# XmasLights.net
KiCad netlist of a schematic drawn in Altium Designer
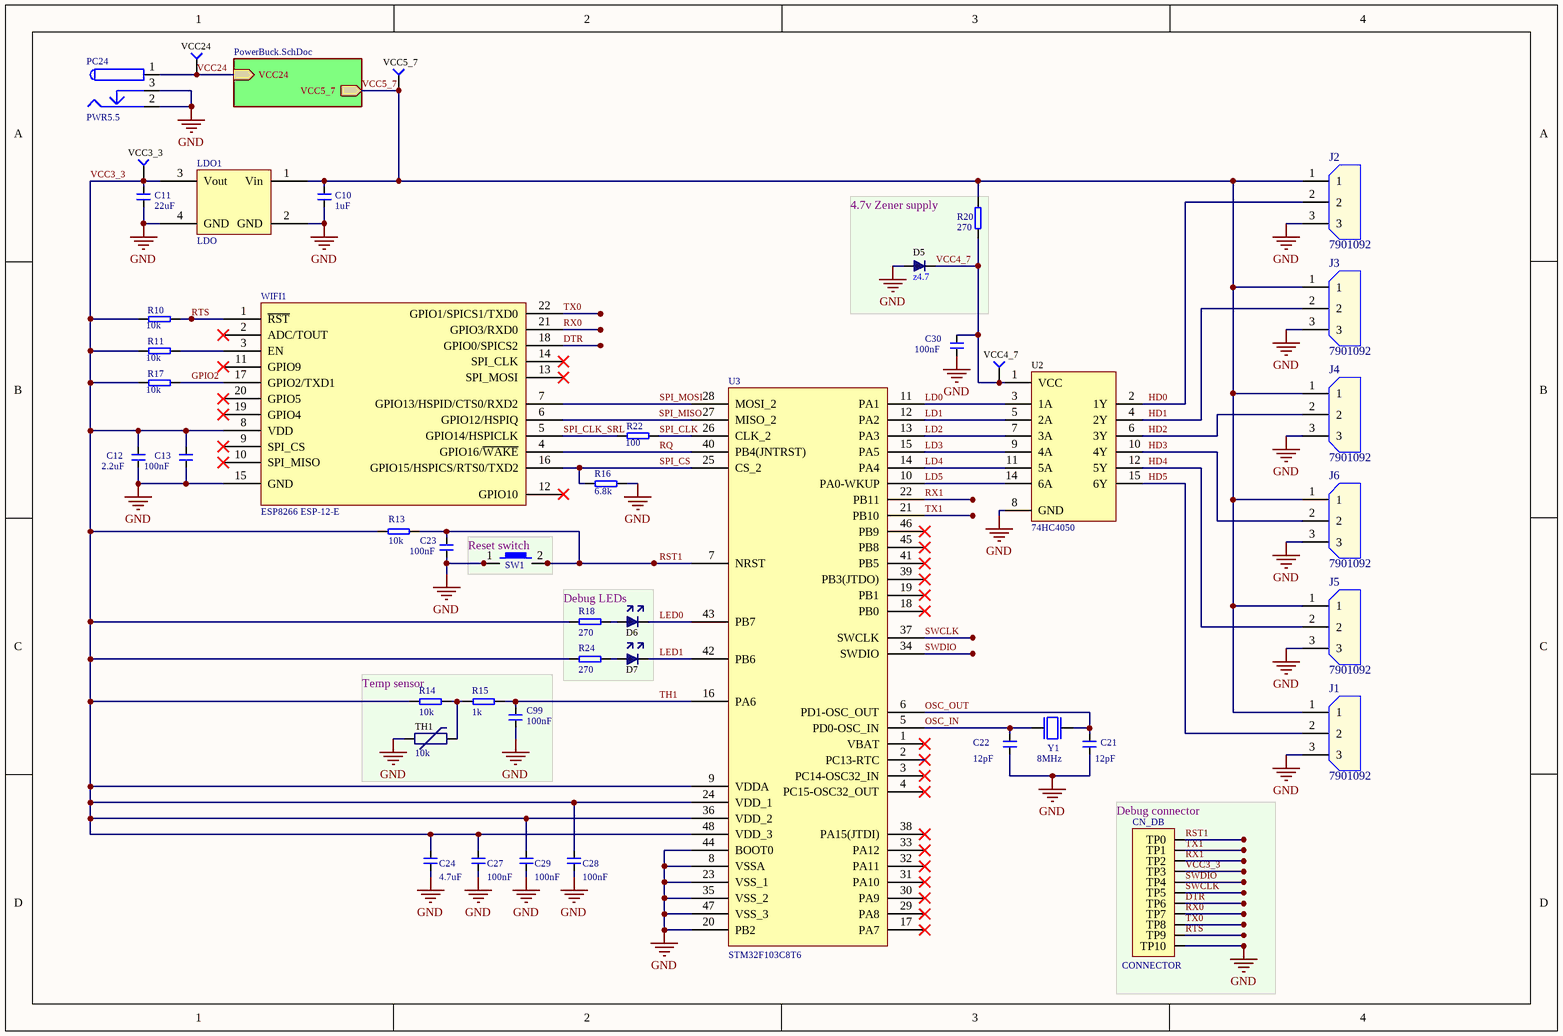
[diagram p0: XmasLights.SchDoc]

(export (version "E")
  (design (tool "Eeschema 10.0.6"))
  (components
    (comp (ref "C10")
      (value "1uF")
      (footprint "CAP_1206")
      (description "Capacitor")
      (libsource (lib "Controller") (part "CAP"))
    )
    (comp (ref "C11")
      (value "22uF")
      (footprint "Controller:CAP_1206")
      (description "Capacitor")
      (libsource (lib "Controller") (part "CAP"))
    )
    (comp (ref "C12")
      (value "2.2uF")
      (footprint "Controller:CAP 0603/1608")
      (description "Capacitor")
      (libsource (lib "Controller") (part "CAP"))
    )
    (comp (ref "C13")
      (value "100nF")
      (footprint "Controller:CAP 0603/1608")
      (description "Capacitor")
      (libsource (lib "Controller") (part "CAP"))
    )
    (comp (ref "C21")
      (value "12pF")
      (footprint "Controller:CAP 0603/1608")
      (description "Capacitor")
      (libsource (lib "Controller") (part "CAP"))
    )
    (comp (ref "C22")
      (value "12pF")
      (footprint "Controller:CAP 0603/1608")
      (description "Capacitor")
      (libsource (lib "Controller") (part "CAP"))
    )
    (comp (ref "C23")
      (value "100nF")
      (footprint "Controller:CAP 0603/1608")
      (description "Capacitor")
      (libsource (lib "Controller") (part "CAP"))
    )
    (comp (ref "C24")
      (value "4.7uF")
      (footprint "Controller:CAP 0603/1608")
      (description "Capacitor")
      (libsource (lib "Controller") (part "CAP"))
    )
    (comp (ref "C27")
      (value "100nF")
      (footprint "Controller:CAP 0603/1608")
      (description "Capacitor")
      (libsource (lib "Controller") (part "CAP"))
    )
    (comp (ref "C28")
      (value "100nF")
      (footprint "Controller:CAP 0603/1608")
      (description "Capacitor")
      (libsource (lib "Controller") (part "CAP"))
    )
    (comp (ref "C29")
      (value "100nF")
      (footprint "Controller:CAP 0603/1608")
      (description "Capacitor")
      (libsource (lib "Controller") (part "CAP"))
    )
    (comp (ref "C30")
      (value "100nF")
      (footprint "Controller:CAP 0603/1608")
      (description "Capacitor")
      (libsource (lib "Controller") (part "CAP"))
    )
    (comp (ref "C99")
      (value "100nF")
      (footprint "Controller:CAP 0603/1608")
      (description "Capacitor")
      (libsource (lib "Controller") (part "CAP"))
    )
    (comp (ref "CN_DB")
      (value "CONNECTOR")
      (footprint "Controller:Edge Connector")
      (description "Debug Connector")
      (libsource (lib "Controller") (part "CONNECTOR"))
    )
    (comp (ref "D5")
      (value "z4.7")
      (footprint "Controller:SOD2512X110N")
      (libsource (lib "Controller") (part "DIODE"))
    )
    (comp (ref "D6")
      (value "LED")
      (footprint "controller:Chip2PinSM127P600-8N")
      (libsource (lib "Controller") (part "LED"))
    )
    (comp (ref "D7")
      (value "LED")
      (footprint "controller:Chip2PinSM127P600-8N")
      (libsource (lib "Controller") (part "LED"))
    )
    (comp (ref "J1") (value "7901092") (footprint "7901092") (libsource (lib "Controller") (part "7901092")))
    (comp (ref "J2") (value "7901092") (footprint "7901092") (libsource (lib "Controller") (part "7901092")))
    (comp (ref "J3") (value "7901092") (footprint "7901092") (libsource (lib "Controller") (part "7901092")))
    (comp (ref "J4") (value "7901092") (footprint "7901092") (libsource (lib "Controller") (part "7901092")))
    (comp (ref "J5") (value "7901092") (footprint "7901092") (libsource (lib "Controller") (part "7901092")))
    (comp (ref "J6") (value "7901092") (footprint "7901092") (libsource (lib "Controller") (part "7901092")))
    (comp (ref "LDO1")
      (value "LDO")
      (footprint "Controller:SOT230P700X180-4N")
      (description "LDO Voltage Regulator")
      (libsource (lib "Controller") (part "LDO"))
    )
    (comp (ref "PC24")
      (value "PWR5.5")
      (footprint "Controller:DC_CON")
      (description "Low Voltage Power Supply Connector")
      (fields (field (name "PUBLISHER") "Altium Limited"))
      (libsource (lib "Controller") (part "PWR2.5"))
    )
    (comp (ref "R10")
      (value "10k")
      (footprint "Controller:RES 0603/1608")
      (description "Resistor")
      (libsource (lib "Controller") (part "RES"))
    )
    (comp (ref "R11")
      (value "10k")
      (footprint "Controller:RES 0603/1608")
      (description "Resistor")
      (libsource (lib "Controller") (part "RES"))
    )
    (comp (ref "R13")
      (value "10k")
      (footprint "Controller:RES 0603/1608")
      (description "Resistor")
      (libsource (lib "Controller") (part "RES"))
    )
    (comp (ref "R14")
      (value "10k")
      (footprint "controller:RES 0603/1608")
      (description "Resistor")
      (libsource (lib "Controller") (part "RES"))
    )
    (comp (ref "R15")
      (value "1k")
      (footprint "controller:RES 0603/1608")
      (description "Resistor")
      (libsource (lib "Controller") (part "RES"))
    )
    (comp (ref "R16")
      (value "6.8k")
      (footprint "Controller:RES 0603/1608")
      (description "Resistor")
      (libsource (lib "Controller") (part "RES"))
    )
    (comp (ref "R17")
      (value "10k")
      (footprint "Controller:RES 0603/1608")
      (description "Resistor")
      (libsource (lib "Controller") (part "RES"))
    )
    (comp (ref "R18")
      (value "270")
      (footprint "Controller:RES 0603/1608")
      (description "Resistor")
      (libsource (lib "Controller") (part "RES"))
    )
    (comp (ref "R20")
      (value "270")
      (footprint "Controller:RES 0603/1608")
      (description "Resistor")
      (libsource (lib "Controller") (part "RES"))
    )
    (comp (ref "R22")
      (value "100")
      (footprint "Controller:RES 0603/1608")
      (description "Resistor")
      (libsource (lib "Controller") (part "RES"))
    )
    (comp (ref "R24")
      (value "270")
      (footprint "Controller:RES 0603/1608")
      (description "Resistor")
      (libsource (lib "Controller") (part "RES"))
    )
    (comp (ref "SW1")
      (value "SWITCH")
      (footprint "Controller:FSM-SWITCH")
      (description "6x6mm SMD tactile switch,5mm H 1.6N Black Button Tactile Switch, SPST-NO 0.05 A@ 12 V dc 1.4mm")
      (fields
        (field (name "RS PART NUMBER") "1616046")
        (field (name "MANUFACTURER_PART_NUMBER") "4-1437565-1")
      )
      (libsource (lib "Controller") (part "4-1437565-1"))
    )
    (comp (ref "TH1")
      (value "10k")
      (footprint "Controller:CAP 0603/1608")
      (libsource (lib "Controller") (part "THERMISTOR"))
    )
    (comp (ref "U2")
      (value "74HC4050")
      (footprint "SOIC127P600X175-16N")
      (libsource (lib "Controller") (part "74HC4050"))
    )
    (comp (ref "U3")
      (value "STM32F103C8T6")
      (footprint "Controller:CQFP50P900X900X160-48N")
      (libsource (lib "Controller") (part "STM32F103C8T6"))
    )
    (comp (ref "VCC3_3")
      (value "TESTPOINT")
      (footprint "TESTPOINT")
      (libsource (lib "Controller") (part "TESTPOINT"))
    )
    (comp (ref "VCC4_7")
      (value "TESTPOINT")
      (footprint "TESTPOINT")
      (libsource (lib "Controller") (part "TESTPOINT"))
    )
    (comp (ref "VCC5_7")
      (value "TESTPOINT")
      (footprint "TESTPOINT")
      (libsource (lib "Controller") (part "TESTPOINT"))
    )
    (comp (ref "VCC24")
      (value "TESTPOINT")
      (footprint "TESTPOINT")
      (libsource (lib "Controller") (part "TESTPOINT"))
    )
    (comp (ref "WIFI1")
      (value "ESP8266 ESP-12-E")
      (footprint "ESP8266:ESP8266 ESP-12-E")
      (libsource (lib "Controller") (part "ESP8266 ESP-12-E"))
    )
    (comp (ref "Y1")
      (value "8MHz")
      (footprint "CRYSTAL")
      (description "Cheapo SMT Crystal")
      (libsource (lib "Controller") (part "CRYSTAL"))
    )
  )
  (nets
    (net (code "1") (name "/DTR") (class "Default")
      (node (ref "CN_DB") (pin "7") (pinfunction "TP6_7") (pintype "passive"))
      (node (ref "WIFI1") (pin "18") (pinfunction "GPIO0/SPICS2_18") (pintype "passive"))
    )
    (net (code "2") (name "/GPIO2") (class "Default")
      (node (ref "R17") (pin "2") (pinfunction "2_2") (pintype "passive"))
      (node (ref "WIFI1") (pin "17") (pinfunction "GPIO2/TXD1_17") (pintype "passive"))
    )
    (net (code "3") (name "/HD0") (class "Default")
      (node (ref "J2") (pin "2") (pinfunction "2_2") (pintype "passive"))
      (node (ref "U2") (pin "2") (pinfunction "1Y_2") (pintype "passive"))
    )
    (net (code "4") (name "/HD1") (class "Default")
      (node (ref "J3") (pin "2") (pinfunction "2_2") (pintype "passive"))
      (node (ref "U2") (pin "4") (pinfunction "2Y_4") (pintype "passive"))
    )
    (net (code "5") (name "/HD2") (class "Default")
      (node (ref "J4") (pin "2") (pinfunction "2_2") (pintype "passive"))
      (node (ref "U2") (pin "6") (pinfunction "3Y_6") (pintype "passive"))
    )
    (net (code "6") (name "/HD3") (class "Default")
      (node (ref "J6") (pin "2") (pinfunction "2_2") (pintype "passive"))
      (node (ref "U2") (pin "10") (pinfunction "4Y_10") (pintype "passive"))
    )
    (net (code "7") (name "/HD4") (class "Default")
      (node (ref "J5") (pin "2") (pinfunction "2_2") (pintype "passive"))
      (node (ref "U2") (pin "12") (pinfunction "5Y_12") (pintype "passive"))
    )
    (net (code "8") (name "/HD5") (class "Default")
      (node (ref "J1") (pin "2") (pinfunction "2_2") (pintype "passive"))
      (node (ref "U2") (pin "15") (pinfunction "6Y_15") (pintype "passive"))
    )
    (net (code "9") (name "/LD0") (class "Default")
      (node (ref "U2") (pin "3") (pinfunction "1A_3") (pintype "passive"))
      (node (ref "U3") (pin "11") (pinfunction "PA1_11") (pintype "passive"))
    )
    (net (code "10") (name "/LD1") (class "Default")
      (node (ref "U2") (pin "5") (pinfunction "2A_5") (pintype "passive"))
      (node (ref "U3") (pin "12") (pinfunction "PA2_12") (pintype "passive"))
    )
    (net (code "11") (name "/LD2") (class "Default")
      (node (ref "U2") (pin "7") (pinfunction "3A_7") (pintype "passive"))
      (node (ref "U3") (pin "13") (pinfunction "PA3_13") (pintype "passive"))
    )
    (net (code "12") (name "/LD3") (class "Default")
      (node (ref "U2") (pin "9") (pinfunction "4A_9") (pintype "passive"))
      (node (ref "U3") (pin "15") (pinfunction "PA5_15") (pintype "passive"))
    )
    (net (code "13") (name "/LD4") (class "Default")
      (node (ref "U2") (pin "11") (pinfunction "5A_11") (pintype "passive"))
      (node (ref "U3") (pin "14") (pinfunction "PA4_14") (pintype "passive"))
    )
    (net (code "14") (name "/LD5") (class "Default")
      (node (ref "U2") (pin "14") (pinfunction "6A_14") (pintype "passive"))
      (node (ref "U3") (pin "10") (pinfunction "PA0-WKUP_10") (pintype "passive"))
    )
    (net (code "15") (name "/LED0") (class "Default")
      (node (ref "D6") (pin "2") (pinfunction "ANODE_2") (pintype "passive"))
      (node (ref "U3") (pin "43") (pinfunction "PB7_43") (pintype "passive"))
    )
    (net (code "16") (name "/LED1") (class "Default")
      (node (ref "D7") (pin "2") (pinfunction "ANODE_2") (pintype "passive"))
      (node (ref "U3") (pin "42") (pinfunction "PB6_42") (pintype "passive"))
    )
    (net (code "17") (name "/OSC_IN") (class "Default")
      (node (ref "C22") (pin "2") (pinfunction "2_2") (pintype "passive"))
      (node (ref "U3") (pin "5") (pinfunction "PD0-OSC_IN_5") (pintype "passive"))
      (node (ref "Y1") (pin "1") (pinfunction "1_1") (pintype "passive"))
    )
    (net (code "18") (name "/OSC_OUT") (class "Default")
      (node (ref "C21") (pin "2") (pinfunction "2_2") (pintype "passive"))
      (node (ref "U3") (pin "6") (pinfunction "PD1-OSC_OUT_6") (pintype "passive"))
      (node (ref "Y1") (pin "2") (pinfunction "2_2") (pintype "passive"))
    )
    (net (code "19") (name "/RQ") (class "Default")
      (node (ref "U3") (pin "40") (pinfunction "PB4(JNTRST)_40") (pintype "passive"))
      (node (ref "WIFI1") (pin "4") (pinfunction "GPIO16/~{WAKE}_4") (pintype "passive"))
    )
    (net (code "20") (name "/RST1") (class "Default")
      (node (ref "C23") (pin "1") (pinfunction "1_1") (pintype "passive"))
      (node (ref "CN_DB") (pin "1") (pinfunction "TP0_1") (pintype "passive"))
      (node (ref "R13") (pin "2") (pinfunction "2_2") (pintype "passive"))
      (node (ref "SW1") (pin "2") (pinfunction "2_2") (pintype "passive"))
      (node (ref "SW1") (pin "4") (pinfunction "4_4") (pintype "passive"))
      (node (ref "U3") (pin "7") (pinfunction "NRST_7") (pintype "passive"))
    )
    (net (code "21") (name "/RTS") (class "Default")
      (node (ref "CN_DB") (pin "10") (pinfunction "TP9_10") (pintype "passive"))
      (node (ref "R10") (pin "2") (pinfunction "2_2") (pintype "passive"))
      (node (ref "WIFI1") (pin "1") (pinfunction "~{RST}_1") (pintype "passive"))
    )
    (net (code "22") (name "/RX0") (class "Default")
      (node (ref "CN_DB") (pin "8") (pinfunction "TP7_8") (pintype "passive"))
      (node (ref "WIFI1") (pin "21") (pinfunction "GPIO3/RXD0_21") (pintype "passive"))
    )
    (net (code "23") (name "/RX1") (class "Default")
      (node (ref "CN_DB") (pin "3") (pinfunction "TP2_3") (pintype "passive"))
      (node (ref "U3") (pin "22") (pinfunction "PB11_22") (pintype "passive"))
    )
    (net (code "24") (name "/SPI_CLK") (class "Default")
      (node (ref "R22") (pin "2") (pinfunction "2_2") (pintype "passive"))
      (node (ref "U3") (pin "26") (pinfunction "CLK_2_26") (pintype "passive"))
    )
    (net (code "25") (name "/SPI_CLK_SRL") (class "Default")
      (node (ref "R22") (pin "1") (pinfunction "1_1") (pintype "passive"))
      (node (ref "WIFI1") (pin "5") (pinfunction "GPIO14/HSPICLK_5") (pintype "passive"))
    )
    (net (code "26") (name "/SPI_CS") (class "Default")
      (node (ref "R16") (pin "2") (pinfunction "2_2") (pintype "passive"))
      (node (ref "U3") (pin "25") (pinfunction "CS_2_25") (pintype "passive"))
      (node (ref "WIFI1") (pin "16") (pinfunction "GPIO15/HSPICS/RTS0/TXD2_16") (pintype "passive"))
    )
    (net (code "27") (name "/SPI_MISO") (class "Default")
      (node (ref "U3") (pin "27") (pinfunction "MISO_2_27") (pintype "passive"))
      (node (ref "WIFI1") (pin "6") (pinfunction "GPIO12/HSPIQ_6") (pintype "passive"))
    )
    (net (code "28") (name "/SPI_MOSI") (class "Default")
      (node (ref "U3") (pin "28") (pinfunction "MOSI_2_28") (pintype "passive"))
      (node (ref "WIFI1") (pin "7") (pinfunction "GPIO13/HSPID/CTS0/RXD2_7") (pintype "passive"))
    )
    (net (code "29") (name "/SWCLK") (class "Default")
      (node (ref "CN_DB") (pin "6") (pinfunction "TP5_6") (pintype "passive"))
      (node (ref "U3") (pin "37") (pinfunction "SWCLK_37") (pintype "passive"))
    )
    (net (code "30") (name "/SWDIO") (class "Default")
      (node (ref "CN_DB") (pin "5") (pinfunction "TP4_5") (pintype "passive"))
      (node (ref "U3") (pin "34") (pinfunction "SWDIO_34") (pintype "passive"))
    )
    (net (code "31") (name "/TH1") (class "Default")
      (node (ref "C99") (pin "2") (pinfunction "2_2") (pintype "passive"))
      (node (ref "R15") (pin "1") (pinfunction "1_1") (pintype "passive"))
      (node (ref "U3") (pin "16") (pinfunction "PA6_16") (pintype "passive"))
    )
    (net (code "32") (name "/TX0") (class "Default")
      (node (ref "CN_DB") (pin "9") (pinfunction "TP8_9") (pintype "passive"))
      (node (ref "WIFI1") (pin "22") (pinfunction "GPIO1/SPICS1/TXD0_22") (pintype "passive"))
    )
    (net (code "33") (name "/TX1") (class "Default")
      (node (ref "CN_DB") (pin "2") (pinfunction "TP1_2") (pintype "passive"))
      (node (ref "U3") (pin "21") (pinfunction "PB10_21") (pintype "passive"))
    )
    (net (code "34") (name "/VCC3_3") (class "Default")
      (node (ref "C11") (pin "1") (pinfunction "1_1") (pintype "passive"))
      (node (ref "C12") (pin "1") (pinfunction "1_1") (pintype "passive"))
      (node (ref "C13") (pin "1") (pinfunction "1_1") (pintype "passive"))
      (node (ref "C24") (pin "1") (pinfunction "1_1") (pintype "passive"))
      (node (ref "C27") (pin "1") (pinfunction "1_1") (pintype "passive"))
      (node (ref "C28") (pin "1") (pinfunction "1_1") (pintype "passive"))
      (node (ref "C29") (pin "1") (pinfunction "1_1") (pintype "passive"))
      (node (ref "CN_DB") (pin "4") (pinfunction "TP3_4") (pintype "passive"))
      (node (ref "LDO1") (pin "3") (pinfunction "Vout_3") (pintype "passive"))
      (node (ref "R10") (pin "1") (pinfunction "1_1") (pintype "passive"))
      (node (ref "R11") (pin "1") (pinfunction "1_1") (pintype "passive"))
      (node (ref "R13") (pin "1") (pinfunction "1_1") (pintype "passive"))
      (node (ref "R14") (pin "1") (pinfunction "1_1") (pintype "passive"))
      (node (ref "R17") (pin "1") (pinfunction "1_1") (pintype "passive"))
      (node (ref "R18") (pin "1") (pinfunction "1_1") (pintype "passive"))
      (node (ref "R24") (pin "1") (pinfunction "1_1") (pintype "passive"))
      (node (ref "U3") (pin "24") (pinfunction "VDD_1_24") (pintype "passive"))
      (node (ref "U3") (pin "36") (pinfunction "VDD_2_36") (pintype "passive"))
      (node (ref "U3") (pin "48") (pinfunction "VDD_3_48") (pintype "passive"))
      (node (ref "U3") (pin "9") (pinfunction "VDDA_9") (pintype "passive"))
      (node (ref "VCC3_3") (pin "1") (pinfunction "1_1") (pintype "passive"))
      (node (ref "WIFI1") (pin "8") (pinfunction "VDD_8") (pintype "passive"))
    )
    (net (code "37") (name "/VCC4_7") (class "Default")
      (node (ref "C30") (pin "1") (pinfunction "1_1") (pintype "passive"))
      (node (ref "D5") (pin "2") (pinfunction "A_2") (pintype "passive"))
      (node (ref "R20") (pin "1") (pinfunction "1_1") (pintype "passive"))
      (node (ref "U2") (pin "1") (pinfunction "VCC_1") (pintype "passive"))
      (node (ref "VCC4_7") (pin "1") (pinfunction "1_1") (pintype "passive"))
    )
    (net (code "38") (name "/VCC5_7_1") (class "Default")
      (node (ref "C10") (pin "1") (pinfunction "1_1") (pintype "passive"))
      (node (ref "J1") (pin "1") (pinfunction "1_1") (pintype "passive"))
      (node (ref "J2") (pin "1") (pinfunction "1_1") (pintype "passive"))
      (node (ref "J3") (pin "1") (pinfunction "1_1") (pintype "passive"))
      (node (ref "J4") (pin "1") (pinfunction "1_1") (pintype "passive"))
      (node (ref "J5") (pin "1") (pinfunction "1_1") (pintype "passive"))
      (node (ref "J6") (pin "1") (pinfunction "1_1") (pintype "passive"))
      (node (ref "LDO1") (pin "1") (pinfunction "Vin_1") (pintype "passive"))
      (node (ref "R20") (pin "2") (pinfunction "2_2") (pintype "passive"))
      (node (ref "VCC5_7") (pin "1") (pinfunction "1_1") (pintype "passive"))
    )
    (net (code "39") (name "/VCC24") (class "Default")
      (node (ref "PC24") (pin "1") (pinfunction "1_1") (pintype "power_in"))
      (node (ref "VCC24") (pin "1") (pinfunction "1_1") (pintype "passive"))
    )
    (net (code "40") (name "GND") (class "Default")
      (node (ref "C10") (pin "2") (pinfunction "2_2") (pintype "passive"))
      (node (ref "C11") (pin "2") (pinfunction "2_2") (pintype "passive"))
      (node (ref "C12") (pin "2") (pinfunction "2_2") (pintype "passive"))
      (node (ref "C13") (pin "2") (pinfunction "2_2") (pintype "passive"))
      (node (ref "C21") (pin "1") (pinfunction "1_1") (pintype "passive"))
      (node (ref "C22") (pin "1") (pinfunction "1_1") (pintype "passive"))
      (node (ref "C23") (pin "2") (pinfunction "2_2") (pintype "passive"))
      (node (ref "C24") (pin "2") (pinfunction "2_2") (pintype "passive"))
      (node (ref "C27") (pin "2") (pinfunction "2_2") (pintype "passive"))
      (node (ref "C28") (pin "2") (pinfunction "2_2") (pintype "passive"))
      (node (ref "C29") (pin "2") (pinfunction "2_2") (pintype "passive"))
      (node (ref "C30") (pin "2") (pinfunction "2_2") (pintype "passive"))
      (node (ref "C99") (pin "1") (pinfunction "1_1") (pintype "passive"))
      (node (ref "CN_DB") (pin "11") (pinfunction "TP10_11") (pintype "passive"))
      (node (ref "D5") (pin "1") (pinfunction "C_1") (pintype "passive"))
      (node (ref "J1") (pin "3") (pinfunction "3_3") (pintype "passive"))
      (node (ref "J2") (pin "3") (pinfunction "3_3") (pintype "passive"))
      (node (ref "J3") (pin "3") (pinfunction "3_3") (pintype "passive"))
      (node (ref "J4") (pin "3") (pinfunction "3_3") (pintype "passive"))
      (node (ref "J5") (pin "3") (pinfunction "3_3") (pintype "passive"))
      (node (ref "J6") (pin "3") (pinfunction "3_3") (pintype "passive"))
      (node (ref "LDO1") (pin "2") (pinfunction "GND_2") (pintype "passive"))
      (node (ref "LDO1") (pin "4") (pinfunction "GND_4") (pintype "passive"))
      (node (ref "PC24") (pin "2") (pinfunction "2_2") (pintype "passive"))
      (node (ref "PC24") (pin "3") (pinfunction "3_3") (pintype "passive"))
      (node (ref "R16") (pin "1") (pinfunction "1_1") (pintype "passive"))
      (node (ref "SW1") (pin "1") (pinfunction "1_1") (pintype "passive"))
      (node (ref "SW1") (pin "3") (pinfunction "3_3") (pintype "passive"))
      (node (ref "TH1") (pin "1") (pinfunction "A_1") (pintype "passive"))
      (node (ref "U2") (pin "8") (pinfunction "GND_8") (pintype "passive"))
      (node (ref "U3") (pin "20") (pinfunction "PB2_20") (pintype "passive"))
      (node (ref "U3") (pin "23") (pinfunction "VSS_1_23") (pintype "passive"))
      (node (ref "U3") (pin "35") (pinfunction "VSS_2_35") (pintype "passive"))
      (node (ref "U3") (pin "44") (pinfunction "BOOT0_44") (pintype "passive"))
      (node (ref "U3") (pin "47") (pinfunction "VSS_3_47") (pintype "passive"))
      (node (ref "U3") (pin "8") (pinfunction "VSSA_8") (pintype "passive"))
      (node (ref "WIFI1") (pin "15") (pinfunction "GND_15") (pintype "passive"))
    )
    (net (code "41") (name "Net-(D6-CATHODE)") (class "Default")
      (node (ref "D6") (pin "1") (pinfunction "CATHODE_1") (pintype "passive"))
      (node (ref "R18") (pin "2") (pinfunction "2_2") (pintype "passive"))
    )
    (net (code "42") (name "Net-(D7-CATHODE)") (class "Default")
      (node (ref "D7") (pin "1") (pinfunction "CATHODE_1") (pintype "passive"))
      (node (ref "R24") (pin "2") (pinfunction "2_2") (pintype "passive"))
    )
    (net (code "43") (name "Net-(R14-Pad2)") (class "Default")
      (node (ref "R14") (pin "2") (pinfunction "2_2") (pintype "passive"))
      (node (ref "R15") (pin "2") (pinfunction "2_2") (pintype "passive"))
      (node (ref "TH1") (pin "2") (pinfunction "A_2") (pintype "passive"))
    )
    (net (code "44") (name "Net-(WIFI1-EN)") (class "Default")
      (node (ref "R11") (pin "2") (pinfunction "2_2") (pintype "passive"))
      (node (ref "WIFI1") (pin "3") (pinfunction "EN_3") (pintype "passive"))
    )
    (net (code "45") (name "unconnected-(U3-PA7-Pad17)") (class "Default")
      (node (ref "U3") (pin "17") (pinfunction "PA7_17") (pintype "passive+no_connect"))
    )
    (net (code "46") (name "unconnected-(U3-PA8-Pad29)") (class "Default")
      (node (ref "U3") (pin "29") (pinfunction "PA8_29") (pintype "passive+no_connect"))
    )
    (net (code "47") (name "unconnected-(U3-PA9-Pad30)") (class "Default")
      (node (ref "U3") (pin "30") (pinfunction "PA9_30") (pintype "passive+no_connect"))
    )
    (net (code "48") (name "unconnected-(U3-PA10-Pad31)") (class "Default")
      (node (ref "U3") (pin "31") (pinfunction "PA10_31") (pintype "passive+no_connect"))
    )
    (net (code "49") (name "unconnected-(U3-PA11-Pad32)") (class "Default")
      (node (ref "U3") (pin "32") (pinfunction "PA11_32") (pintype "passive+no_connect"))
    )
    (net (code "50") (name "unconnected-(U3-PA12-Pad33)") (class "Default")
      (node (ref "U3") (pin "33") (pinfunction "PA12_33") (pintype "passive+no_connect"))
    )
    (net (code "51") (name "unconnected-(U3-PA15(JTDI)-Pad38)") (class "Default")
      (node (ref "U3") (pin "38") (pinfunction "PA15(JTDI)_38") (pintype "passive+no_connect"))
    )
    (net (code "52") (name "unconnected-(U3-PB0-Pad18)") (class "Default")
      (node (ref "U3") (pin "18") (pinfunction "PB0_18") (pintype "passive+no_connect"))
    )
    (net (code "53") (name "unconnected-(U3-PB1-Pad19)") (class "Default")
      (node (ref "U3") (pin "19") (pinfunction "PB1_19") (pintype "passive+no_connect"))
    )
    (net (code "54") (name "unconnected-(U3-PB3(JTDO)-Pad39)") (class "Default")
      (node (ref "U3") (pin "39") (pinfunction "PB3(JTDO)_39") (pintype "passive+no_connect"))
    )
    (net (code "55") (name "unconnected-(U3-PB5-Pad41)") (class "Default")
      (node (ref "U3") (pin "41") (pinfunction "PB5_41") (pintype "passive+no_connect"))
    )
    (net (code "56") (name "unconnected-(U3-PB8-Pad45)") (class "Default")
      (node (ref "U3") (pin "45") (pinfunction "PB8_45") (pintype "passive+no_connect"))
    )
    (net (code "57") (name "unconnected-(U3-PB9-Pad46)") (class "Default")
      (node (ref "U3") (pin "46") (pinfunction "PB9_46") (pintype "passive+no_connect"))
    )
    (net (code "58") (name "unconnected-(U3-PC13-RTC-Pad2)") (class "Default")
      (node (ref "U3") (pin "2") (pinfunction "PC13-RTC_2") (pintype "passive+no_connect"))
    )
    (net (code "59") (name "unconnected-(U3-PC14-OSC32_IN-Pad3)") (class "Default")
      (node (ref "U3") (pin "3") (pinfunction "PC14-OSC32_IN_3") (pintype "passive+no_connect"))
    )
    (net (code "60") (name "unconnected-(U3-PC15-OSC32_OUT-Pad4)") (class "Default")
      (node (ref "U3") (pin "4") (pinfunction "PC15-OSC32_OUT_4") (pintype "passive+no_connect"))
    )
    (net (code "61") (name "unconnected-(U3-VBAT-Pad1)") (class "Default")
      (node (ref "U3") (pin "1") (pinfunction "VBAT_1") (pintype "passive+no_connect"))
    )
    (net (code "62") (name "unconnected-(WIFI1-ADC{slash}TOUT-Pad2)") (class "Default")
      (node (ref "WIFI1") (pin "2") (pinfunction "ADC/TOUT_2") (pintype "passive+no_connect"))
    )
    (net (code "63") (name "unconnected-(WIFI1-GPIO4-Pad19)") (class "Default")
      (node (ref "WIFI1") (pin "19") (pinfunction "GPIO4_19") (pintype "passive+no_connect"))
    )
    (net (code "64") (name "unconnected-(WIFI1-GPIO5-Pad20)") (class "Default")
      (node (ref "WIFI1") (pin "20") (pinfunction "GPIO5_20") (pintype "passive+no_connect"))
    )
    (net (code "65") (name "unconnected-(WIFI1-GPIO9-Pad11)") (class "Default")
      (node (ref "WIFI1") (pin "11") (pinfunction "GPIO9_11") (pintype "passive+no_connect"))
    )
    (net (code "66") (name "unconnected-(WIFI1-GPIO10-Pad12)") (class "Default")
      (node (ref "WIFI1") (pin "12") (pinfunction "GPIO10_12") (pintype "passive+no_connect"))
    )
    (net (code "67") (name "unconnected-(WIFI1-SPI_CLK-Pad14)") (class "Default")
      (node (ref "WIFI1") (pin "14") (pinfunction "SPI_CLK_14") (pintype "passive+no_connect"))
    )
    (net (code "68") (name "unconnected-(WIFI1-SPI_CS-Pad9)") (class "Default")
      (node (ref "WIFI1") (pin "9") (pinfunction "SPI_CS_9") (pintype "passive+no_connect"))
    )
    (net (code "69") (name "unconnected-(WIFI1-SPI_MISO-Pad10)") (class "Default")
      (node (ref "WIFI1") (pin "10") (pinfunction "SPI_MISO_10") (pintype "passive+no_connect"))
    )
    (net (code "70") (name "unconnected-(WIFI1-SPI_MOSI-Pad13)") (class "Default")
      (node (ref "WIFI1") (pin "13") (pinfunction "SPI_MOSI_13") (pintype "passive+no_connect"))
    )
  )
)
